# B684J.net
KiCad netlist of a schematic drawn in EAGLE
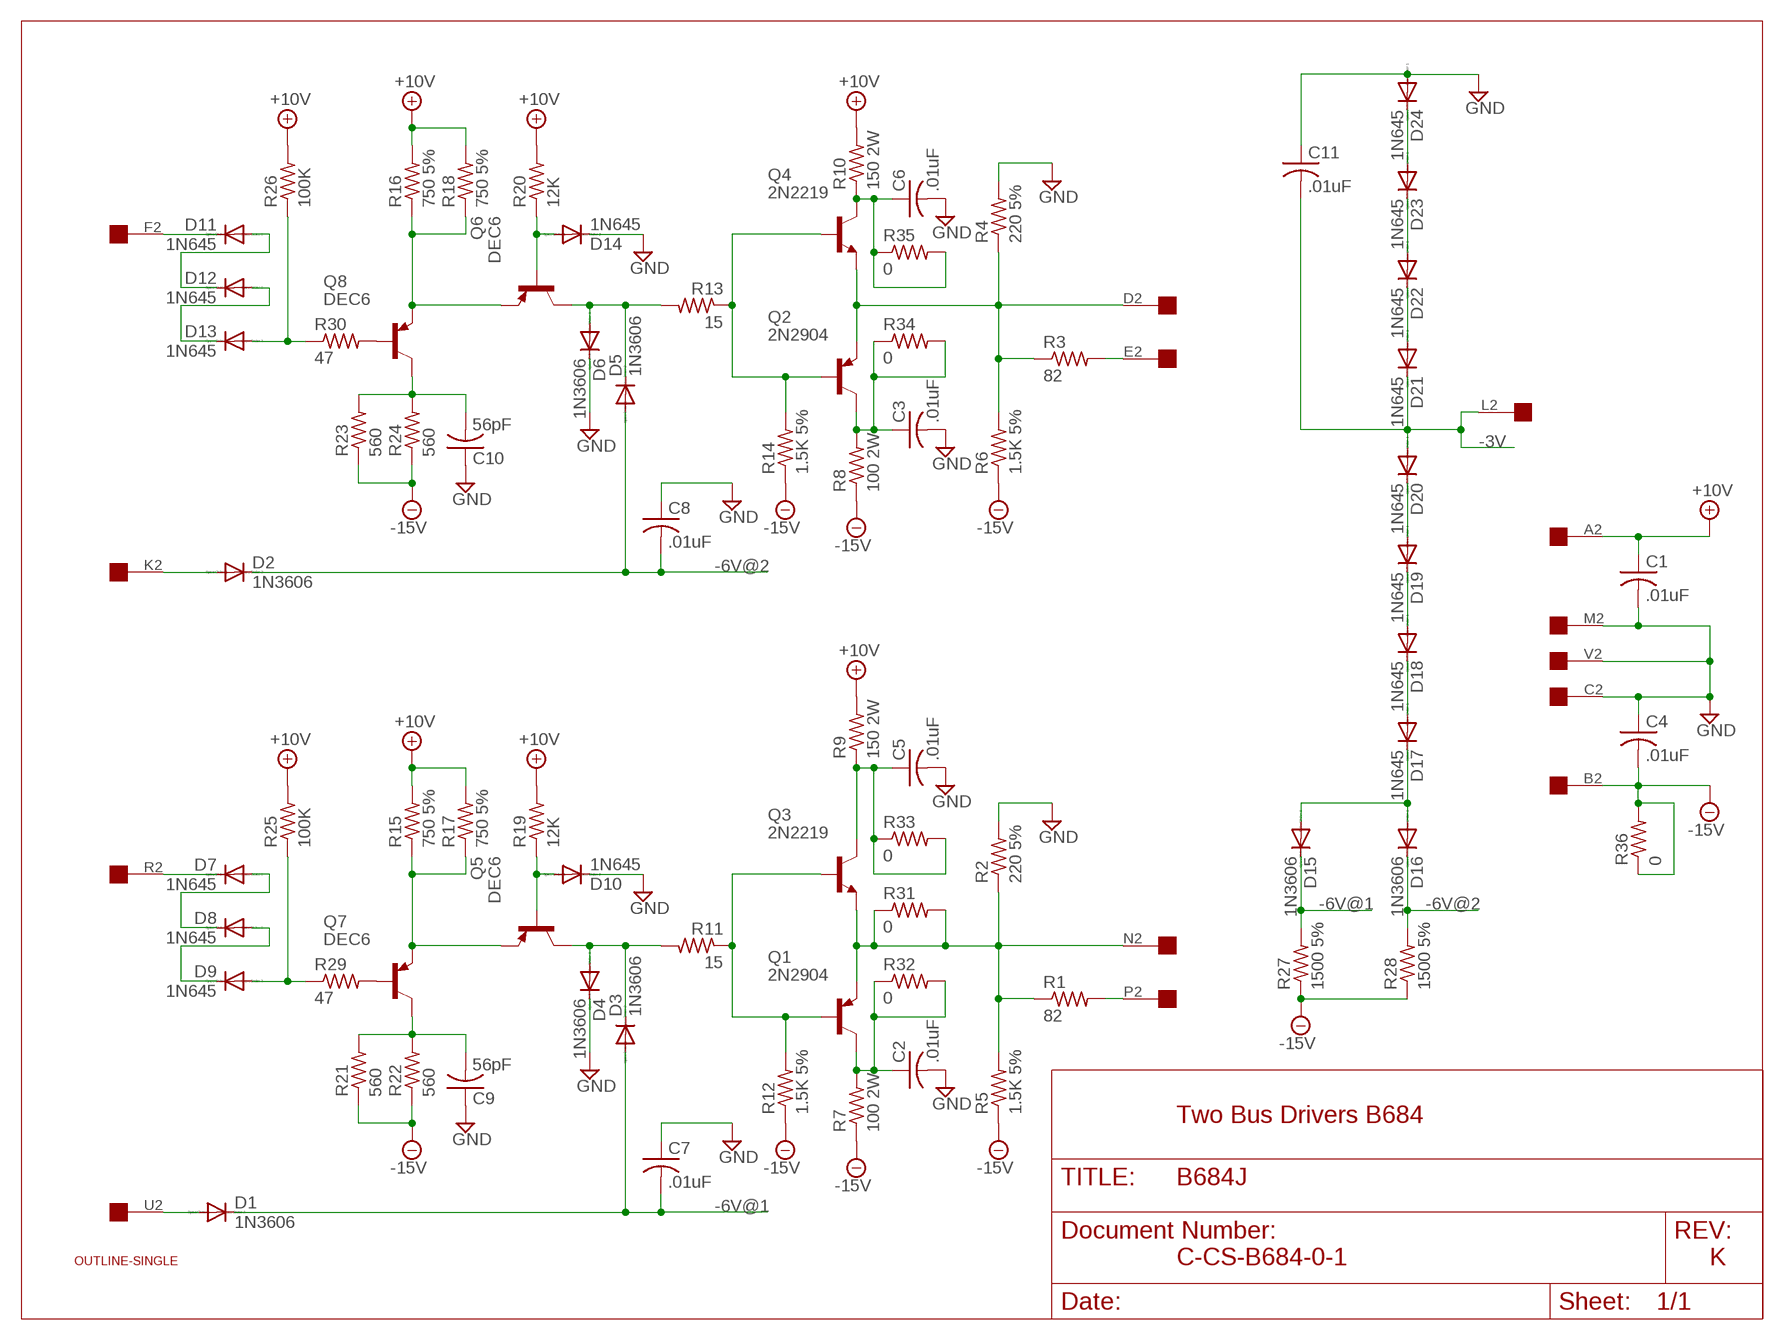
[diagram p0: schematic, sheet 1]

(export (version "E")
  (design (tool "Eeschema 10.0.6"))
  (components
    (comp (ref "C1")
      (value ".01uF")
      (footprint "eagle-import:C063-025X075")
      (libsource (lib "eagle-import") (part "C-US"))
    )
    (comp (ref "C2")
      (value ".01uF")
      (footprint "eagle-import:C063-025X075")
      (libsource (lib "eagle-import") (part "C-US"))
    )
    (comp (ref "C3")
      (value ".01uF")
      (footprint "eagle-import:C063-025X075")
      (libsource (lib "eagle-import") (part "C-US"))
    )
    (comp (ref "C4")
      (value ".01uF")
      (footprint "eagle-import:C063-025X075")
      (libsource (lib "eagle-import") (part "C-US"))
    )
    (comp (ref "C5")
      (value ".01uF")
      (footprint "eagle-import:C063-025X075")
      (libsource (lib "eagle-import") (part "C-US"))
    )
    (comp (ref "C6")
      (value ".01uF")
      (footprint "eagle-import:C063-025X075")
      (libsource (lib "eagle-import") (part "C-US"))
    )
    (comp (ref "C7")
      (value ".01uF")
      (footprint "eagle-import:C063-025X075")
      (libsource (lib "eagle-import") (part "C-US"))
    )
    (comp (ref "C8")
      (value ".01uF")
      (footprint "eagle-import:C063-025X075")
      (libsource (lib "eagle-import") (part "C-US"))
    )
    (comp (ref "C9")
      (value "56pF")
      (footprint "eagle-import:C063-025X075")
      (libsource (lib "eagle-import") (part "C-US"))
    )
    (comp (ref "C10")
      (value "56pF")
      (footprint "eagle-import:C063-025X075")
      (libsource (lib "eagle-import") (part "C-US"))
    )
    (comp (ref "C11")
      (value ".01uF")
      (footprint "eagle-import:C063-025X075")
      (libsource (lib "eagle-import") (part "C-US"))
    )
    (comp (ref "D1")
      (value "1N3606")
      (footprint "eagle-import:DO35-10")
      (libsource (lib "eagle-import") (part "1N4148DO35-10"))
    )
    (comp (ref "D2")
      (value "1N3606")
      (footprint "eagle-import:DO35-10")
      (libsource (lib "eagle-import") (part "1N4148DO35-10"))
    )
    (comp (ref "D3")
      (value "1N3606")
      (footprint "eagle-import:DO35-10")
      (libsource (lib "eagle-import") (part "1N4148DO35-10"))
    )
    (comp (ref "D4")
      (value "1N3606")
      (footprint "eagle-import:DO35-10")
      (libsource (lib "eagle-import") (part "1N4148DO35-10"))
    )
    (comp (ref "D5")
      (value "1N3606")
      (footprint "eagle-import:DO35-10")
      (libsource (lib "eagle-import") (part "1N4148DO35-10"))
    )
    (comp (ref "D6")
      (value "1N3606")
      (footprint "eagle-import:DO35-10")
      (libsource (lib "eagle-import") (part "1N4148DO35-10"))
    )
    (comp (ref "D7")
      (value "1N645")
      (footprint "eagle-import:DO35-10")
      (libsource (lib "eagle-import") (part "1N4148DO35-10"))
    )
    (comp (ref "D8")
      (value "1N645")
      (footprint "eagle-import:DO35-10")
      (libsource (lib "eagle-import") (part "1N4148DO35-10"))
    )
    (comp (ref "D9")
      (value "1N645")
      (footprint "eagle-import:DO35-10")
      (libsource (lib "eagle-import") (part "DIODE-DO35-10"))
    )
    (comp (ref "D10")
      (value "1N645")
      (footprint "eagle-import:DO35-10")
      (libsource (lib "eagle-import") (part "1N4148DO35-10"))
    )
    (comp (ref "D11")
      (value "1N645")
      (footprint "eagle-import:DO35-10")
      (libsource (lib "eagle-import") (part "1N4148DO35-10"))
    )
    (comp (ref "D12")
      (value "1N645")
      (footprint "eagle-import:DO35-10")
      (libsource (lib "eagle-import") (part "1N4148DO35-10"))
    )
    (comp (ref "D13")
      (value "1N645")
      (footprint "eagle-import:DO35-10")
      (libsource (lib "eagle-import") (part "DIODE-DO35-10"))
    )
    (comp (ref "D14")
      (value "1N645")
      (footprint "eagle-import:DO35-10")
      (libsource (lib "eagle-import") (part "1N4148DO35-10"))
    )
    (comp (ref "D15")
      (value "1N3606")
      (footprint "eagle-import:DO35-10")
      (libsource (lib "eagle-import") (part "1N4148DO35-10"))
    )
    (comp (ref "D16")
      (value "1N3606")
      (footprint "eagle-import:DO35-10")
      (libsource (lib "eagle-import") (part "1N4148DO35-10"))
    )
    (comp (ref "D17")
      (value "1N645")
      (footprint "eagle-import:DO35-10")
      (libsource (lib "eagle-import") (part "1N4148DO35-10"))
    )
    (comp (ref "D18")
      (value "1N645")
      (footprint "eagle-import:DO35-10")
      (libsource (lib "eagle-import") (part "1N4148DO35-10"))
    )
    (comp (ref "D19")
      (value "1N645")
      (footprint "eagle-import:DO35-10")
      (libsource (lib "eagle-import") (part "1N4148DO35-10"))
    )
    (comp (ref "D20")
      (value "1N645")
      (footprint "eagle-import:DO35-10")
      (libsource (lib "eagle-import") (part "1N4148DO35-10"))
    )
    (comp (ref "D21")
      (value "1N645")
      (footprint "eagle-import:DO35-10")
      (libsource (lib "eagle-import") (part "1N4148DO35-10"))
    )
    (comp (ref "D22")
      (value "1N645")
      (footprint "eagle-import:DO35-10")
      (libsource (lib "eagle-import") (part "1N4148DO35-10"))
    )
    (comp (ref "D23")
      (value "1N645")
      (footprint "eagle-import:DO35-10")
      (libsource (lib "eagle-import") (part "1N4148DO35-10"))
    )
    (comp (ref "D24")
      (value "1N645")
      (footprint "eagle-import:DO35-10")
      (libsource (lib "eagle-import") (part "1N4148DO35-10"))
    )
    (comp (ref "Q1")
      (value "2N2904")
      (footprint "eagle-import:TO39")
      (libsource (lib "eagle-import") (part "2N3637"))
    )
    (comp (ref "Q2")
      (value "2N2904")
      (footprint "eagle-import:TO39")
      (libsource (lib "eagle-import") (part "2N3637"))
    )
    (comp (ref "Q3")
      (value "2N2219")
      (footprint "eagle-import:TO5")
      (libsource (lib "eagle-import") (part "2N2219"))
    )
    (comp (ref "Q4")
      (value "2N2219")
      (footprint "eagle-import:TO5")
      (libsource (lib "eagle-import") (part "2N2219"))
    )
    (comp (ref "Q5")
      (value "DEC6")
      (footprint "eagle-import:TO39")
      (libsource (lib "eagle-import") (part "2N3637"))
    )
    (comp (ref "Q6")
      (value "DEC6")
      (footprint "eagle-import:TO39")
      (libsource (lib "eagle-import") (part "2N3637"))
    )
    (comp (ref "Q7")
      (value "DEC6")
      (footprint "eagle-import:TO39")
      (libsource (lib "eagle-import") (part "2N3637"))
    )
    (comp (ref "Q8")
      (value "DEC6")
      (footprint "eagle-import:TO39")
      (libsource (lib "eagle-import") (part "2N3637"))
    )
    (comp (ref "R1")
      (value "82")
      (footprint "eagle-import:0207_10")
      (libsource (lib "eagle-import") (part "R-US_0207/10"))
    )
    (comp (ref "R2")
      (value "220 5%")
      (footprint "eagle-import:0207_10")
      (libsource (lib "eagle-import") (part "R-US_0207/10"))
    )
    (comp (ref "R3")
      (value "82")
      (footprint "eagle-import:0207_10")
      (libsource (lib "eagle-import") (part "R-US_0207/10"))
    )
    (comp (ref "R4")
      (value "220 5%")
      (footprint "eagle-import:0207_10")
      (libsource (lib "eagle-import") (part "R-US_0207/10"))
    )
    (comp (ref "R5")
      (value "1.5K 5%")
      (footprint "eagle-import:0207_10")
      (libsource (lib "eagle-import") (part "R-US_0207/10"))
    )
    (comp (ref "R6")
      (value "1.5K 5%")
      (footprint "eagle-import:0207_10")
      (libsource (lib "eagle-import") (part "R-US_0207/10"))
    )
    (comp (ref "R7")
      (value "100 2W")
      (footprint "eagle-import:P0817_22")
      (libsource (lib "eagle-import") (part "R-US_0817/22"))
    )
    (comp (ref "R8")
      (value "100 2W")
      (footprint "eagle-import:P0817_22")
      (libsource (lib "eagle-import") (part "R-US_0817/22"))
    )
    (comp (ref "R9")
      (value "150 2W")
      (footprint "eagle-import:P0817_22")
      (libsource (lib "eagle-import") (part "R-US_0817/22"))
    )
    (comp (ref "R10")
      (value "150 2W")
      (footprint "eagle-import:P0817_22")
      (libsource (lib "eagle-import") (part "R-US_0817/22"))
    )
    (comp (ref "R11")
      (value "15")
      (footprint "eagle-import:0207_10")
      (libsource (lib "eagle-import") (part "R-US_0207/10"))
    )
    (comp (ref "R12")
      (value "1.5K 5%")
      (footprint "eagle-import:0207_10")
      (libsource (lib "eagle-import") (part "R-US_0207/10"))
    )
    (comp (ref "R13")
      (value "15")
      (footprint "eagle-import:0207_10")
      (libsource (lib "eagle-import") (part "R-US_0207/10"))
    )
    (comp (ref "R14")
      (value "1.5K 5%")
      (footprint "eagle-import:0207_10")
      (libsource (lib "eagle-import") (part "R-US_0207/10"))
    )
    (comp (ref "R15")
      (value "750 5%")
      (footprint "eagle-import:0207_10")
      (libsource (lib "eagle-import") (part "R-US_0207/10"))
    )
    (comp (ref "R16")
      (value "750 5%")
      (footprint "eagle-import:0207_10")
      (libsource (lib "eagle-import") (part "R-US_0207/10"))
    )
    (comp (ref "R17")
      (value "750 5%")
      (footprint "eagle-import:0207_10")
      (libsource (lib "eagle-import") (part "R-US_0207/10"))
    )
    (comp (ref "R18")
      (value "750 5%")
      (footprint "eagle-import:0207_10")
      (libsource (lib "eagle-import") (part "R-US_0207/10"))
    )
    (comp (ref "R19")
      (value "12K")
      (footprint "eagle-import:0207_10")
      (libsource (lib "eagle-import") (part "R-US_0207/10"))
    )
    (comp (ref "R20")
      (value "12K")
      (footprint "eagle-import:0207_10")
      (libsource (lib "eagle-import") (part "R-US_0207/10"))
    )
    (comp (ref "R21")
      (value "560")
      (footprint "eagle-import:0207_10")
      (libsource (lib "eagle-import") (part "R-US_0207/10"))
    )
    (comp (ref "R22")
      (value "560")
      (footprint "eagle-import:0207_10")
      (libsource (lib "eagle-import") (part "R-US_0207/10"))
    )
    (comp (ref "R23")
      (value "560")
      (footprint "eagle-import:0207_10")
      (libsource (lib "eagle-import") (part "R-US_0207/10"))
    )
    (comp (ref "R24")
      (value "560")
      (footprint "eagle-import:0207_10")
      (libsource (lib "eagle-import") (part "R-US_0207/10"))
    )
    (comp (ref "R25")
      (value "100K")
      (footprint "eagle-import:0207_10")
      (libsource (lib "eagle-import") (part "R-US_0207/10"))
    )
    (comp (ref "R26")
      (value "100K")
      (footprint "eagle-import:0207_10")
      (libsource (lib "eagle-import") (part "R-US_0207/10"))
    )
    (comp (ref "R27")
      (value "1500 5%")
      (footprint "eagle-import:0207_10")
      (libsource (lib "eagle-import") (part "R-US_0207/10"))
    )
    (comp (ref "R28")
      (value "1500 5%")
      (footprint "eagle-import:0207_10")
      (libsource (lib "eagle-import") (part "R-US_0207/10"))
    )
    (comp (ref "R29")
      (value "47")
      (footprint "eagle-import:0207_10")
      (libsource (lib "eagle-import") (part "R-US_0207/10"))
    )
    (comp (ref "R30")
      (value "47")
      (footprint "eagle-import:0207_10")
      (libsource (lib "eagle-import") (part "R-US_0207/10"))
    )
    (comp (ref "R31")
      (value "0")
      (footprint "eagle-import:0207_10")
      (libsource (lib "eagle-import") (part "R-US_0207/10"))
    )
    (comp (ref "R32")
      (value "0")
      (footprint "eagle-import:0207_10")
      (libsource (lib "eagle-import") (part "R-US_0207/10"))
    )
    (comp (ref "R33")
      (value "0")
      (footprint "eagle-import:0207_10")
      (libsource (lib "eagle-import") (part "R-US_0207/10"))
    )
    (comp (ref "R34")
      (value "0")
      (footprint "eagle-import:0207_10")
      (libsource (lib "eagle-import") (part "R-US_0207/10"))
    )
    (comp (ref "R35")
      (value "0")
      (footprint "eagle-import:0207_10")
      (libsource (lib "eagle-import") (part "R-US_0207/10"))
    )
    (comp (ref "R36")
      (value "0")
      (footprint "eagle-import:0207_10")
      (libsource (lib "eagle-import") (part "R-US_0207/10"))
    )
    (comp (ref "U$1")
      (value "OUTLINE-SINGLE")
      (footprint "eagle-import:SINGLE")
      (libsource (lib "eagle-import") (part "OUTLINE-SINGLE"))
    )
    (comp (ref "U$2")
      (value "EDGE-1")
      (footprint "eagle-import:EDGE-CON1")
      (libsource (lib "eagle-import") (part "EDGE-1"))
    )
  )
  (nets
    (net (code "1") (name "+10V") (class "Default")
      (node (ref "C1") (pin "1") (pinfunction "1_1") (pintype "passive"))
      (node (ref "R10") (pin "2") (pinfunction "2_2") (pintype "passive"))
      (node (ref "R15") (pin "2") (pinfunction "2_2") (pintype "passive"))
      (node (ref "R16") (pin "2") (pinfunction "2_2") (pintype "passive"))
      (node (ref "R17") (pin "2") (pinfunction "2_2") (pintype "passive"))
      (node (ref "R18") (pin "2") (pinfunction "2_2") (pintype "passive"))
      (node (ref "R19") (pin "2") (pinfunction "2_2") (pintype "passive"))
      (node (ref "R20") (pin "2") (pinfunction "2_2") (pintype "passive"))
      (node (ref "R25") (pin "2") (pinfunction "2_2") (pintype "passive"))
      (node (ref "R26") (pin "2") (pinfunction "2_2") (pintype "passive"))
      (node (ref "R9") (pin "2") (pinfunction "2_2") (pintype "passive"))
      (node (ref "U$2") (pin "A2") (pinfunction "1_A2") (pintype "bidirectional"))
    )
    (net (code "2") (name "-15V") (class "Default")
      (node (ref "C4") (pin "2") (pinfunction "2_2") (pintype "passive"))
      (node (ref "R12") (pin "1") (pinfunction "1_1") (pintype "passive"))
      (node (ref "R14") (pin "1") (pinfunction "1_1") (pintype "passive"))
      (node (ref "R21") (pin "1") (pinfunction "1_1") (pintype "passive"))
      (node (ref "R22") (pin "1") (pinfunction "1_1") (pintype "passive"))
      (node (ref "R23") (pin "1") (pinfunction "1_1") (pintype "passive"))
      (node (ref "R24") (pin "1") (pinfunction "1_1") (pintype "passive"))
      (node (ref "R27") (pin "1") (pinfunction "1_1") (pintype "passive"))
      (node (ref "R28") (pin "1") (pinfunction "1_1") (pintype "passive"))
      (node (ref "R36") (pin "1") (pinfunction "1_1") (pintype "passive"))
      (node (ref "R36") (pin "2") (pinfunction "2_2") (pintype "passive"))
      (node (ref "R5") (pin "1") (pinfunction "1_1") (pintype "passive"))
      (node (ref "R6") (pin "1") (pinfunction "1_1") (pintype "passive"))
      (node (ref "R7") (pin "1") (pinfunction "1_1") (pintype "passive"))
      (node (ref "R8") (pin "1") (pinfunction "1_1") (pintype "passive"))
      (node (ref "U$2") (pin "B2") (pinfunction "1_B2") (pintype "bidirectional"))
    )
    (net (code "3") (name "/-3V") (class "Default")
      (node (ref "C11") (pin "2") (pinfunction "2_2") (pintype "passive"))
      (node (ref "D20") (pin "A") (pinfunction "A_A") (pintype "passive"))
      (node (ref "D21") (pin "C") (pinfunction "C_C") (pintype "passive"))
      (node (ref "U$2") (pin "L2") (pinfunction "1_L2") (pintype "bidirectional"))
    )
    (net (code "4") (name "/-6V@1") (class "Default")
      (node (ref "C7") (pin "2") (pinfunction "2_2") (pintype "passive"))
      (node (ref "D1") (pin "C") (pinfunction "C_C") (pintype "passive"))
      (node (ref "D15") (pin "C") (pinfunction "C_C") (pintype "passive"))
      (node (ref "D3") (pin "A") (pinfunction "A_A") (pintype "passive"))
      (node (ref "R27") (pin "2") (pinfunction "2_2") (pintype "passive"))
    )
    (net (code "5") (name "/-6V@2") (class "Default")
      (node (ref "C8") (pin "2") (pinfunction "2_2") (pintype "passive"))
      (node (ref "D16") (pin "C") (pinfunction "C_C") (pintype "passive"))
      (node (ref "D2") (pin "C") (pinfunction "C_C") (pintype "passive"))
      (node (ref "D5") (pin "A") (pinfunction "A_A") (pintype "passive"))
      (node (ref "R28") (pin "2") (pinfunction "2_2") (pintype "passive"))
    )
    (net (code "6") (name "GND") (class "Default")
      (node (ref "C1") (pin "2") (pinfunction "2_2") (pintype "passive"))
      (node (ref "C10") (pin "1") (pinfunction "1_1") (pintype "passive"))
      (node (ref "C11") (pin "1") (pinfunction "1_1") (pintype "passive"))
      (node (ref "C2") (pin "2") (pinfunction "2_2") (pintype "passive"))
      (node (ref "C3") (pin "2") (pinfunction "2_2") (pintype "passive"))
      (node (ref "C4") (pin "1") (pinfunction "1_1") (pintype "passive"))
      (node (ref "C5") (pin "2") (pinfunction "2_2") (pintype "passive"))
      (node (ref "C6") (pin "2") (pinfunction "2_2") (pintype "passive"))
      (node (ref "C7") (pin "1") (pinfunction "1_1") (pintype "passive"))
      (node (ref "C8") (pin "1") (pinfunction "1_1") (pintype "passive"))
      (node (ref "C9") (pin "1") (pinfunction "1_1") (pintype "passive"))
      (node (ref "D10") (pin "C") (pinfunction "C_C") (pintype "passive"))
      (node (ref "D14") (pin "C") (pinfunction "C_C") (pintype "passive"))
      (node (ref "D24") (pin "A") (pinfunction "A_A") (pintype "passive"))
      (node (ref "D4") (pin "C") (pinfunction "C_C") (pintype "passive"))
      (node (ref "D6") (pin "C") (pinfunction "C_C") (pintype "passive"))
      (node (ref "R2") (pin "2") (pinfunction "2_2") (pintype "passive"))
      (node (ref "R4") (pin "2") (pinfunction "2_2") (pintype "passive"))
      (node (ref "U$2") (pin "C2") (pinfunction "1_C2") (pintype "bidirectional"))
      (node (ref "U$2") (pin "M2") (pinfunction "1_M2") (pintype "bidirectional"))
      (node (ref "U$2") (pin "V2") (pinfunction "1_V2") (pintype "bidirectional"))
    )
    (net (code "7") (name "Net-(D7-PadA)") (class "Default")
      (node (ref "D7") (pin "A") (pinfunction "A_A") (pintype "passive"))
      (node (ref "D8") (pin "C") (pinfunction "C_C") (pintype "passive"))
    )
    (net (code "8") (name "Net-(D8-PadA)") (class "Default")
      (node (ref "D8") (pin "A") (pinfunction "A_A") (pintype "passive"))
      (node (ref "D9") (pin "C") (pinfunction "C_C") (pintype "passive"))
    )
    (net (code "9") (name "Net-(D9-PadA)") (class "Default")
      (node (ref "D9") (pin "A") (pinfunction "A_A") (pintype "passive"))
      (node (ref "R25") (pin "1") (pinfunction "1_1") (pintype "passive"))
      (node (ref "R29") (pin "1") (pinfunction "1_1") (pintype "passive"))
    )
    (net (code "10") (name "Net-(D11-PadA)") (class "Default")
      (node (ref "D11") (pin "A") (pinfunction "A_A") (pintype "passive"))
      (node (ref "D12") (pin "C") (pinfunction "C_C") (pintype "passive"))
    )
    (net (code "11") (name "Net-(D12-PadA)") (class "Default")
      (node (ref "D12") (pin "A") (pinfunction "A_A") (pintype "passive"))
      (node (ref "D13") (pin "C") (pinfunction "C_C") (pintype "passive"))
    )
    (net (code "12") (name "Net-(D13-PadA)") (class "Default")
      (node (ref "D13") (pin "A") (pinfunction "A_A") (pintype "passive"))
      (node (ref "R26") (pin "1") (pinfunction "1_1") (pintype "passive"))
      (node (ref "R30") (pin "1") (pinfunction "1_1") (pintype "passive"))
    )
    (net (code "13") (name "Net-(D15-PadA)") (class "Default")
      (node (ref "D15") (pin "A") (pinfunction "A_A") (pintype "passive"))
      (node (ref "D16") (pin "A") (pinfunction "A_A") (pintype "passive"))
      (node (ref "D17") (pin "C") (pinfunction "C_C") (pintype "passive"))
    )
    (net (code "14") (name "Net-(D17-PadA)") (class "Default")
      (node (ref "D17") (pin "A") (pinfunction "A_A") (pintype "passive"))
      (node (ref "D18") (pin "C") (pinfunction "C_C") (pintype "passive"))
    )
    (net (code "15") (name "Net-(D18-PadA)") (class "Default")
      (node (ref "D18") (pin "A") (pinfunction "A_A") (pintype "passive"))
      (node (ref "D19") (pin "C") (pinfunction "C_C") (pintype "passive"))
    )
    (net (code "16") (name "Net-(D19-PadA)") (class "Default")
      (node (ref "D19") (pin "A") (pinfunction "A_A") (pintype "passive"))
      (node (ref "D20") (pin "C") (pinfunction "C_C") (pintype "passive"))
    )
    (net (code "17") (name "Net-(D21-PadA)") (class "Default")
      (node (ref "D21") (pin "A") (pinfunction "A_A") (pintype "passive"))
      (node (ref "D22") (pin "C") (pinfunction "C_C") (pintype "passive"))
    )
    (net (code "18") (name "Net-(D22-PadA)") (class "Default")
      (node (ref "D22") (pin "A") (pinfunction "A_A") (pintype "passive"))
      (node (ref "D23") (pin "C") (pinfunction "C_C") (pintype "passive"))
    )
    (net (code "19") (name "Net-(D23-PadA)") (class "Default")
      (node (ref "D23") (pin "A") (pinfunction "A_A") (pintype "passive"))
      (node (ref "D24") (pin "C") (pinfunction "C_C") (pintype "passive"))
    )
    (net (code "20") (name "Net-(Q1-B)") (class "Default")
      (node (ref "Q1") (pin "2") (pinfunction "B_2") (pintype "passive"))
      (node (ref "Q3") (pin "2") (pinfunction "B_2") (pintype "passive"))
      (node (ref "R11") (pin "1") (pinfunction "1_1") (pintype "passive"))
      (node (ref "R12") (pin "2") (pinfunction "2_2") (pintype "passive"))
    )
    (net (code "21") (name "Net-(Q1-C)") (class "Default")
      (node (ref "C2") (pin "1") (pinfunction "1_1") (pintype "passive"))
      (node (ref "Q1") (pin "3") (pinfunction "C_3") (pintype "passive"))
      (node (ref "R32") (pin "1") (pinfunction "1_1") (pintype "passive"))
      (node (ref "R32") (pin "2") (pinfunction "2_2") (pintype "passive"))
      (node (ref "R7") (pin "2") (pinfunction "2_2") (pintype "passive"))
    )
    (net (code "22") (name "Net-(Q1-E)") (class "Default")
      (node (ref "Q1") (pin "1") (pinfunction "E_1") (pintype "passive"))
      (node (ref "Q3") (pin "1") (pinfunction "E_1") (pintype "passive"))
      (node (ref "R1") (pin "1") (pinfunction "1_1") (pintype "passive"))
      (node (ref "R2") (pin "1") (pinfunction "1_1") (pintype "passive"))
      (node (ref "R31") (pin "1") (pinfunction "1_1") (pintype "passive"))
      (node (ref "R31") (pin "2") (pinfunction "2_2") (pintype "passive"))
      (node (ref "R5") (pin "2") (pinfunction "2_2") (pintype "passive"))
      (node (ref "U$2") (pin "N2") (pinfunction "1_N2") (pintype "bidirectional"))
    )
    (net (code "23") (name "Net-(Q2-B)") (class "Default")
      (node (ref "Q2") (pin "2") (pinfunction "B_2") (pintype "passive"))
      (node (ref "Q4") (pin "2") (pinfunction "B_2") (pintype "passive"))
      (node (ref "R13") (pin "1") (pinfunction "1_1") (pintype "passive"))
      (node (ref "R14") (pin "2") (pinfunction "2_2") (pintype "passive"))
    )
    (net (code "24") (name "Net-(Q2-C)") (class "Default")
      (node (ref "C3") (pin "1") (pinfunction "1_1") (pintype "passive"))
      (node (ref "Q2") (pin "3") (pinfunction "C_3") (pintype "passive"))
      (node (ref "R34") (pin "1") (pinfunction "1_1") (pintype "passive"))
      (node (ref "R34") (pin "2") (pinfunction "2_2") (pintype "passive"))
      (node (ref "R8") (pin "2") (pinfunction "2_2") (pintype "passive"))
    )
    (net (code "25") (name "Net-(Q2-E)") (class "Default")
      (node (ref "Q2") (pin "1") (pinfunction "E_1") (pintype "passive"))
      (node (ref "Q4") (pin "1") (pinfunction "E_1") (pintype "passive"))
      (node (ref "R3") (pin "1") (pinfunction "1_1") (pintype "passive"))
      (node (ref "R4") (pin "1") (pinfunction "1_1") (pintype "passive"))
      (node (ref "R6") (pin "2") (pinfunction "2_2") (pintype "passive"))
      (node (ref "U$2") (pin "D2") (pinfunction "1_D2") (pintype "bidirectional"))
    )
    (net (code "26") (name "Net-(Q3-C)") (class "Default")
      (node (ref "C5") (pin "1") (pinfunction "1_1") (pintype "passive"))
      (node (ref "Q3") (pin "3") (pinfunction "C_3") (pintype "passive"))
      (node (ref "R33") (pin "1") (pinfunction "1_1") (pintype "passive"))
      (node (ref "R33") (pin "2") (pinfunction "2_2") (pintype "passive"))
      (node (ref "R9") (pin "1") (pinfunction "1_1") (pintype "passive"))
    )
    (net (code "27") (name "Net-(Q4-C)") (class "Default")
      (node (ref "C6") (pin "1") (pinfunction "1_1") (pintype "passive"))
      (node (ref "Q4") (pin "3") (pinfunction "C_3") (pintype "passive"))
      (node (ref "R10") (pin "1") (pinfunction "1_1") (pintype "passive"))
      (node (ref "R35") (pin "1") (pinfunction "1_1") (pintype "passive"))
      (node (ref "R35") (pin "2") (pinfunction "2_2") (pintype "passive"))
    )
    (net (code "28") (name "Net-(Q5-B)") (class "Default")
      (node (ref "D10") (pin "A") (pinfunction "A_A") (pintype "passive"))
      (node (ref "Q5") (pin "2") (pinfunction "B_2") (pintype "passive"))
      (node (ref "R19") (pin "1") (pinfunction "1_1") (pintype "passive"))
    )
    (net (code "29") (name "Net-(Q5-C)") (class "Default")
      (node (ref "D3") (pin "C") (pinfunction "C_C") (pintype "passive"))
      (node (ref "D4") (pin "A") (pinfunction "A_A") (pintype "passive"))
      (node (ref "Q5") (pin "3") (pinfunction "C_3") (pintype "passive"))
      (node (ref "R11") (pin "2") (pinfunction "2_2") (pintype "passive"))
    )
    (net (code "30") (name "Net-(Q5-E)") (class "Default")
      (node (ref "Q5") (pin "1") (pinfunction "E_1") (pintype "passive"))
      (node (ref "Q7") (pin "1") (pinfunction "E_1") (pintype "passive"))
      (node (ref "R15") (pin "1") (pinfunction "1_1") (pintype "passive"))
      (node (ref "R17") (pin "1") (pinfunction "1_1") (pintype "passive"))
    )
    (net (code "31") (name "Net-(Q6-B)") (class "Default")
      (node (ref "D14") (pin "A") (pinfunction "A_A") (pintype "passive"))
      (node (ref "Q6") (pin "2") (pinfunction "B_2") (pintype "passive"))
      (node (ref "R20") (pin "1") (pinfunction "1_1") (pintype "passive"))
    )
    (net (code "32") (name "Net-(Q6-C)") (class "Default")
      (node (ref "D5") (pin "C") (pinfunction "C_C") (pintype "passive"))
      (node (ref "D6") (pin "A") (pinfunction "A_A") (pintype "passive"))
      (node (ref "Q6") (pin "3") (pinfunction "C_3") (pintype "passive"))
      (node (ref "R13") (pin "2") (pinfunction "2_2") (pintype "passive"))
    )
    (net (code "33") (name "Net-(Q6-E)") (class "Default")
      (node (ref "Q6") (pin "1") (pinfunction "E_1") (pintype "passive"))
      (node (ref "Q8") (pin "1") (pinfunction "E_1") (pintype "passive"))
      (node (ref "R16") (pin "1") (pinfunction "1_1") (pintype "passive"))
      (node (ref "R18") (pin "1") (pinfunction "1_1") (pintype "passive"))
    )
    (net (code "34") (name "Net-(Q7-B)") (class "Default")
      (node (ref "Q7") (pin "2") (pinfunction "B_2") (pintype "passive"))
      (node (ref "R29") (pin "2") (pinfunction "2_2") (pintype "passive"))
    )
    (net (code "35") (name "Net-(Q7-C)") (class "Default")
      (node (ref "C9") (pin "2") (pinfunction "2_2") (pintype "passive"))
      (node (ref "Q7") (pin "3") (pinfunction "C_3") (pintype "passive"))
      (node (ref "R21") (pin "2") (pinfunction "2_2") (pintype "passive"))
      (node (ref "R22") (pin "2") (pinfunction "2_2") (pintype "passive"))
    )
    (net (code "36") (name "Net-(Q8-B)") (class "Default")
      (node (ref "Q8") (pin "2") (pinfunction "B_2") (pintype "passive"))
      (node (ref "R30") (pin "2") (pinfunction "2_2") (pintype "passive"))
    )
    (net (code "37") (name "Net-(Q8-C)") (class "Default")
      (node (ref "C10") (pin "2") (pinfunction "2_2") (pintype "passive"))
      (node (ref "Q8") (pin "3") (pinfunction "C_3") (pintype "passive"))
      (node (ref "R23") (pin "2") (pinfunction "2_2") (pintype "passive"))
      (node (ref "R24") (pin "2") (pinfunction "2_2") (pintype "passive"))
    )
    (net (code "38") (name "Net-(U$2E-1)") (class "Default")
      (node (ref "R3") (pin "2") (pinfunction "2_2") (pintype "passive"))
      (node (ref "U$2") (pin "E2") (pinfunction "1_E2") (pintype "bidirectional"))
    )
    (net (code "39") (name "Net-(U$2F-1)") (class "Default")
      (node (ref "D11") (pin "C") (pinfunction "C_C") (pintype "passive"))
      (node (ref "U$2") (pin "F2") (pinfunction "1_F2") (pintype "bidirectional"))
    )
    (net (code "40") (name "Net-(U$2I-1)") (class "Default")
      (node (ref "D2") (pin "A") (pinfunction "A_A") (pintype "passive"))
      (node (ref "U$2") (pin "K2") (pinfunction "1_K2") (pintype "bidirectional"))
    )
    (net (code "41") (name "Net-(U$2M-1)") (class "Default")
      (node (ref "R1") (pin "2") (pinfunction "2_2") (pintype "passive"))
      (node (ref "U$2") (pin "P2") (pinfunction "1_P2") (pintype "bidirectional"))
    )
    (net (code "42") (name "Net-(U$2N-1)") (class "Default")
      (node (ref "D7") (pin "C") (pinfunction "C_C") (pintype "passive"))
      (node (ref "U$2") (pin "R2") (pinfunction "1_R2") (pintype "bidirectional"))
    )
    (net (code "43") (name "Net-(U$2Q-1)") (class "Default")
      (node (ref "D1") (pin "A") (pinfunction "A_A") (pintype "passive"))
      (node (ref "U$2") (pin "U2") (pinfunction "1_U2") (pintype "bidirectional"))
    )
  )
)
